# nguon.net
KiCad netlist of a schematic drawn in Altium Designer
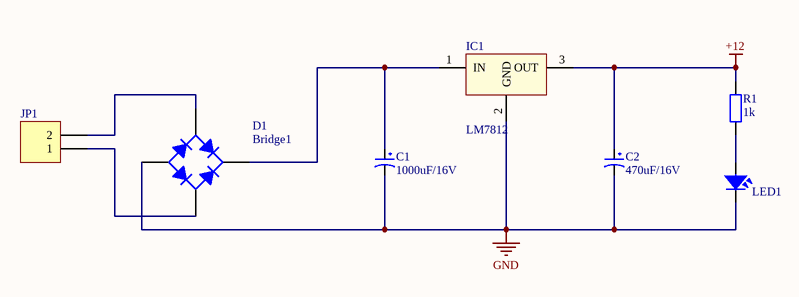
[diagram p0: nguon.SchDoc]

(export (version "E")
  (design (tool "Eeschema 10.0.6"))
  (components
    (comp (ref "C1")
      (value "1000uF/16V")
      (footprint "CP1.5/3.4")
      (description "Cap 1000uF/16V - 220uF/50V")
      (libsource (lib "syhaunguyen") (part "CP4"))
    )
    (comp (ref "C2")
      (value "470uF/16V")
      (footprint "CP1.5/3.4")
      (description "Cap 1000uF/16V - 220uF/50V")
      (libsource (lib "syhaunguyen") (part "CP4"))
    )
    (comp (ref "D1")
      (value "Bridge1")
      (footprint "D-38")
      (description "Full Wave Diode Bridge")
      (fields (field (name "PUBLISHER") "Altium Limited"))
      (libsource (lib "Miscellaneous Devices") (part "Bridge1"))
    )
    (comp (ref "IC1")
      (value "LM7812")
      (footprint "QTO-220")
      (description "On ap +, from + 5 to + 24VDC")
      (libsource (lib "syhaunguyen") (part "LM78xx"))
    )
    (comp (ref "JP1")
      (value "Header 2")
      (footprint "CON2")
      (description "Header, 2-Pin")
      (fields (field (name "MANUFACTURER") "Generic Components"))
      (libsource (lib "syhaunguyen") (part "Header 2"))
    )
    (comp (ref "LED1")
      (value "LED")
      (footprint "LED-3")
      (description "LED Single colour Green and Red")
      (libsource (lib "syhaunguyen") (part "LED"))
    )
    (comp (ref "R1")
      (value "1k")
      (footprint "R1/4W")
      (description "Resistor 1/4W")
      (libsource (lib "syhaunguyen") (part "R1/4W"))
    )
  )
  (nets
    (net (code "1") (name "+12") (class "Default")
      (node (ref "C2") (pin "1") (pinfunction "1_1") (pintype "passive"))
      (node (ref "IC1") (pin "3") (pinfunction "OUT_3") (pintype "passive"))
      (node (ref "R1") (pin "2") (pinfunction "2_2") (pintype "passive"))
    )
    (net (code "2") (name "GND") (class "Default")
      (node (ref "C1") (pin "2") (pinfunction "2_2") (pintype "passive"))
      (node (ref "C2") (pin "2") (pinfunction "2_2") (pintype "passive"))
      (node (ref "D1") (pin "3") (pinfunction "A_3") (pintype "passive"))
      (node (ref "IC1") (pin "2") (pinfunction "GND_2") (pintype "passive"))
      (node (ref "LED1") (pin "2") (pinfunction "2_2") (pintype "passive"))
    )
    (net (code "3") (name "Net-(D1-C-Pad2)") (class "Default")
      (node (ref "D1") (pin "2") (pinfunction "C_2") (pintype "passive"))
      (node (ref "JP1") (pin "1") (pinfunction "1_1") (pintype "passive"))
    )
    (net (code "4") (name "Net-(D1-C-Pad4)") (class "Default")
      (node (ref "D1") (pin "4") (pinfunction "C_4") (pintype "passive"))
      (node (ref "JP1") (pin "2") (pinfunction "2_2") (pintype "passive"))
    )
    (net (code "5") (name "Net-(D1-K)") (class "Default")
      (node (ref "C1") (pin "1") (pinfunction "1_1") (pintype "passive"))
      (node (ref "D1") (pin "1") (pinfunction "K_1") (pintype "passive"))
      (node (ref "IC1") (pin "1") (pinfunction "IN_1") (pintype "passive"))
    )
    (net (code "6") (name "Net-(LED1-Pad1)") (class "Default")
      (node (ref "LED1") (pin "1") (pinfunction "1_1") (pintype "passive"))
      (node (ref "R1") (pin "1") (pinfunction "1_1") (pintype "passive"))
    )
  )
)
